# 4_PowerSupplie.net
KiCad netlist of a schematic drawn in Altium Designer
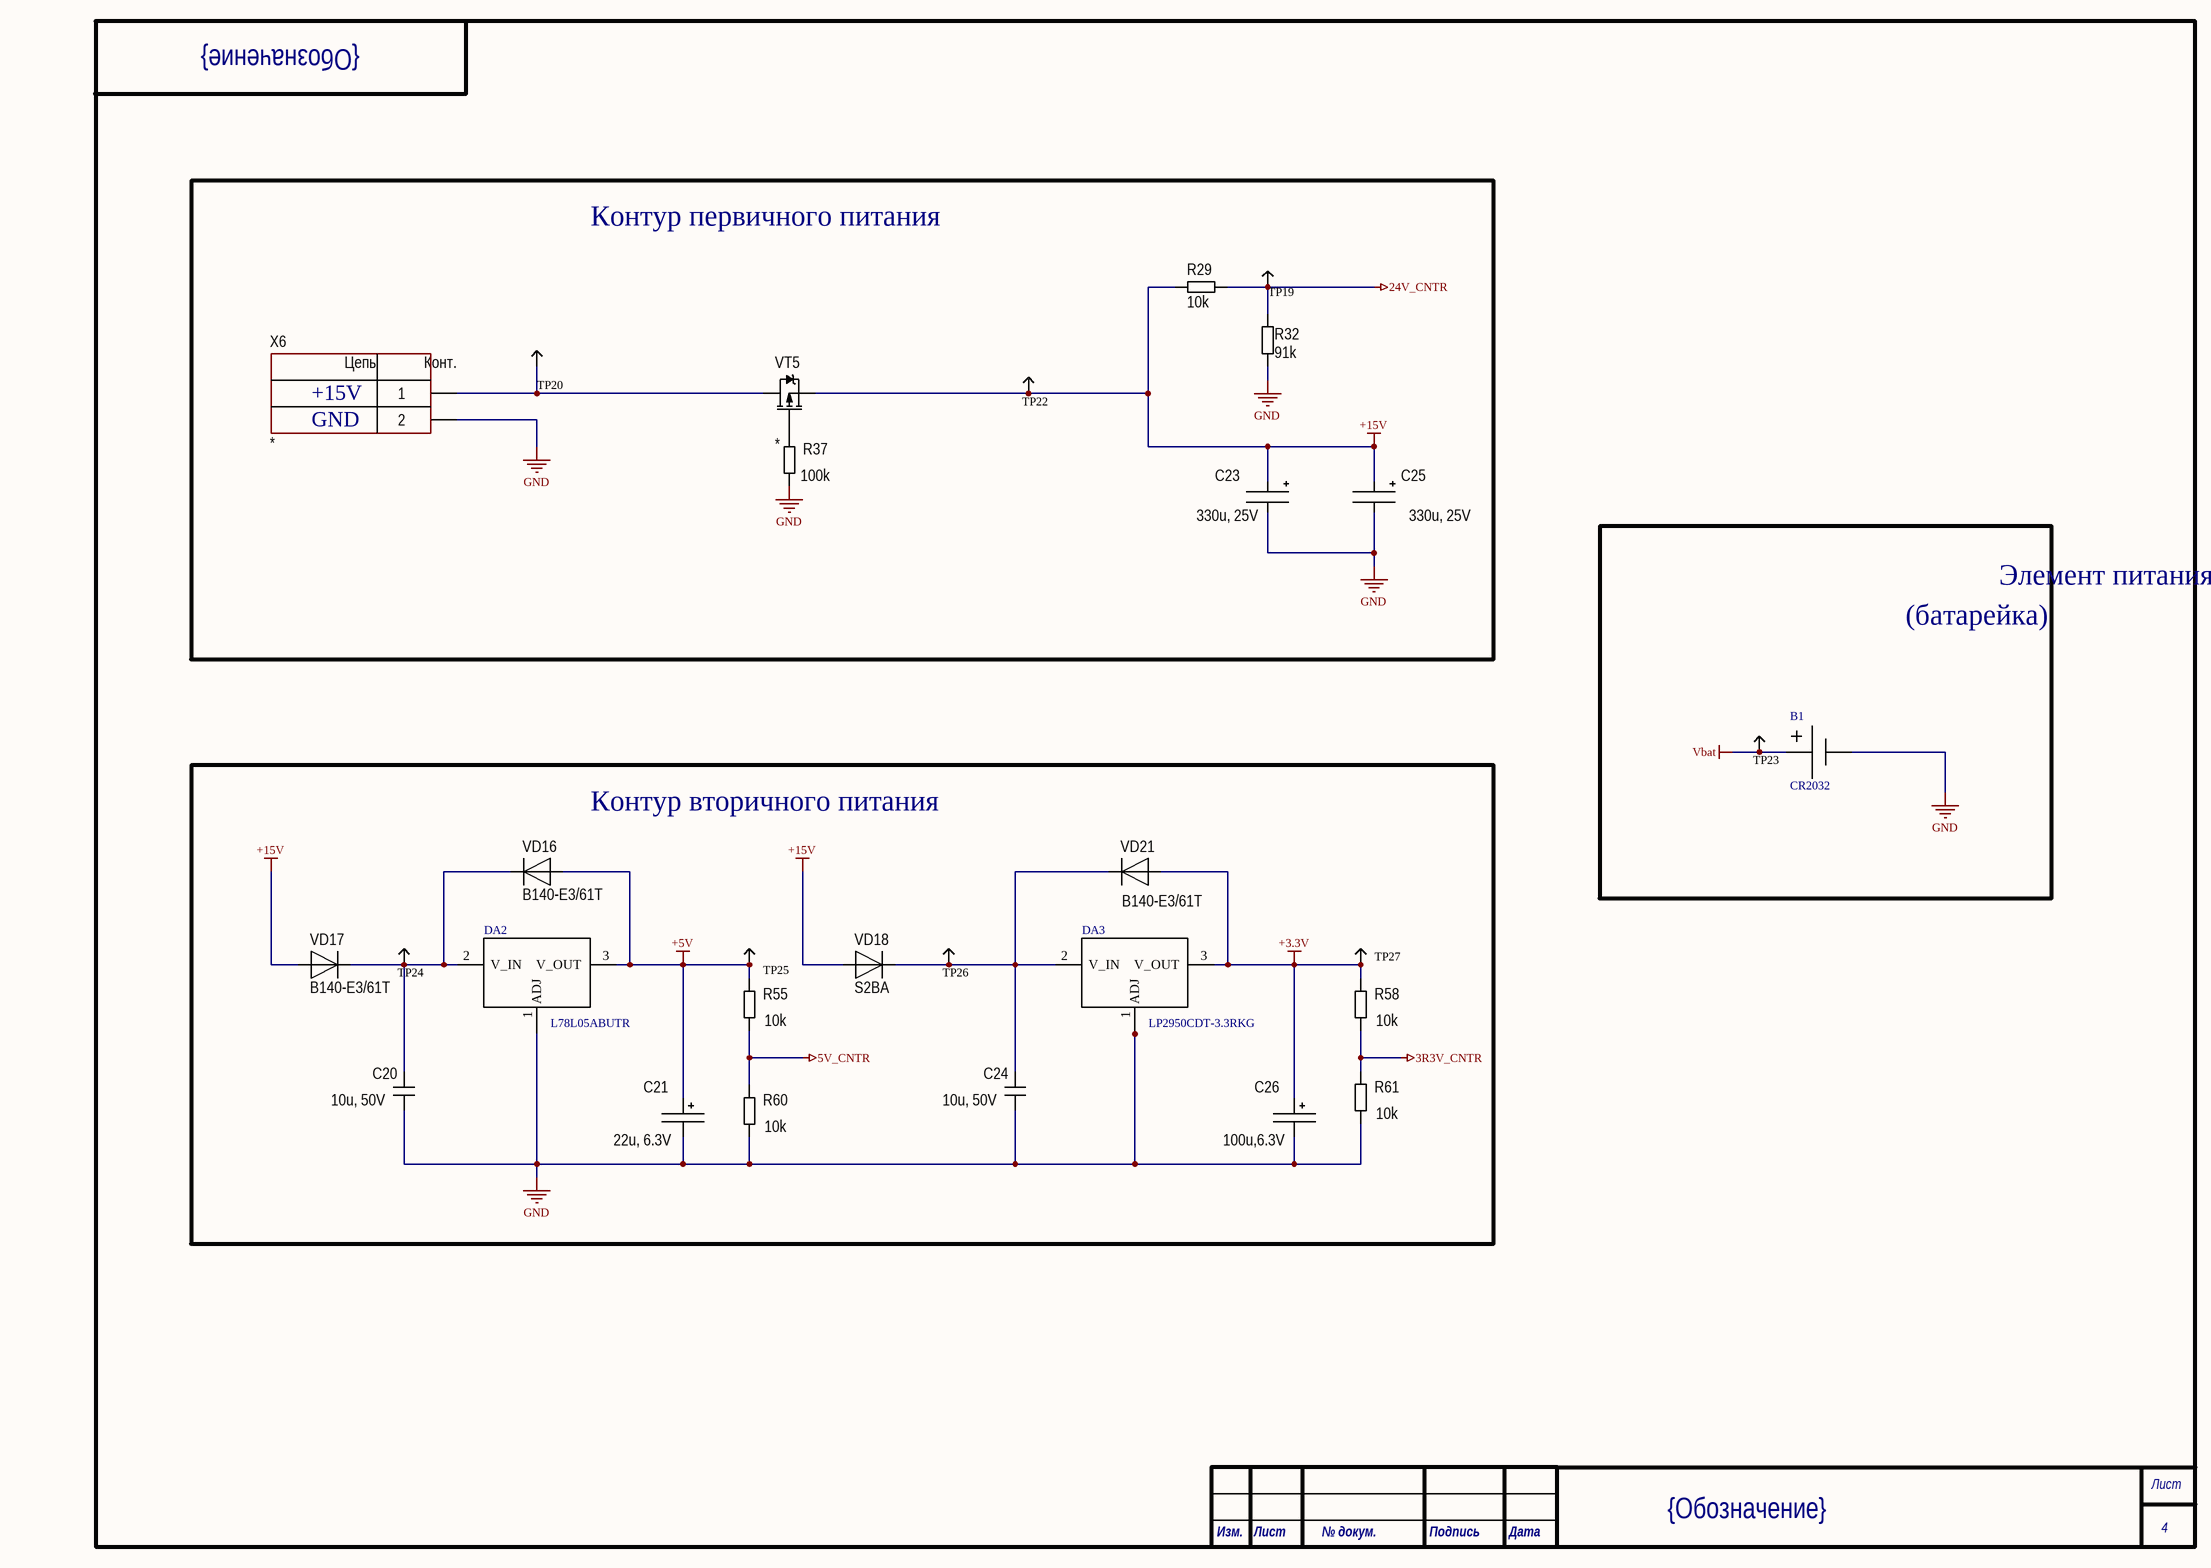
[diagram p0: 4_PowerSupplie.SchDoc]

(export (version "E")
  (design (tool "Eeschema 10.0.6"))
  (components
    (comp (ref "B1")
      (value "CR2032")
      (footprint "BAT: CR2032_SM")
      (libsource (lib "Melochi") (part "Battery_CR2032"))
    )
    (comp (ref "C20")
      (value "10u, 50V")
      (footprint "CH1206C")
      (libsource (lib "Condensators") (part "Capacitor"))
    )
    (comp (ref "C21")
      (value "22u, 6.3V")
      (footprint "TANTAL_A")
      (libsource (lib "Condensators") (part "TantalCap"))
    )
    (comp (ref "C23")
      (value "330u, 25V")
      (footprint "D10C4.4H10")
      (libsource (lib "Condensators") (part "AlumCap"))
    )
    (comp (ref "C24")
      (value "10u, 50V")
      (footprint "CH1206C")
      (libsource (lib "Condensators") (part "Capacitor"))
    )
    (comp (ref "C25")
      (value "330u, 25V")
      (footprint "D10C4.4H10")
      (libsource (lib "Condensators") (part "AlumCap"))
    )
    (comp (ref "C26")
      (value "100u,6.3V")
      (footprint "TANTAL_B")
      (libsource (lib "Condensators") (part "TantalCap"))
    )
    (comp (ref "DA2")
      (value "L78L05ABUTR")
      (footprint "SOT89_PC12120")
      (libsource (lib "MicroIC") (part "LM1117"))
    )
    (comp (ref "DA3")
      (value "LP2950CDT-3.3RKG")
      (footprint "DPAK_213")
      (libsource (lib "MicroIC") (part "LM1117"))
    )
    (comp (ref "R29") (value "10k") (footprint "CH0402R") (libsource (lib "Resistors") (part "Resistor")))
    (comp (ref "R32") (value "91k") (footprint "CH0402R") (libsource (lib "Resistors") (part "Resistor")))
    (comp (ref "R37") (value "100k") (footprint "CH0402R") (libsource (lib "Resistors") (part "Resistor")))
    (comp (ref "R55") (value "10k") (footprint "CH0402R") (libsource (lib "Resistors") (part "Resistor")))
    (comp (ref "R58") (value "10k") (footprint "CH0402R") (libsource (lib "Resistors") (part "Resistor")))
    (comp (ref "R60") (value "10k") (footprint "CH0402R") (libsource (lib "Resistors") (part "Resistor")))
    (comp (ref "R61") (value "10k") (footprint "CH0402R") (libsource (lib "Resistors") (part "Resistor")))
    (comp (ref "TP19") (value "~") (footprint "TestPoint") (libsource (lib "Melochi") (part "TestPoint")))
    (comp (ref "TP20") (value "~") (footprint "TestPoint") (libsource (lib "Melochi") (part "TestPoint")))
    (comp (ref "TP22") (value "~") (footprint "TestPoint") (libsource (lib "Melochi") (part "TestPoint")))
    (comp (ref "TP23") (value "~") (footprint "TestPoint") (libsource (lib "Melochi") (part "TestPoint")))
    (comp (ref "TP24") (value "~") (footprint "TestPoint") (libsource (lib "Melochi") (part "TestPoint")))
    (comp (ref "TP25") (value "~") (footprint "TestPoint") (libsource (lib "Melochi") (part "TestPoint")))
    (comp (ref "TP26") (value "~") (footprint "TestPoint") (libsource (lib "Melochi") (part "TestPoint")))
    (comp (ref "TP27") (value "~") (footprint "TestPoint") (libsource (lib "Melochi") (part "TestPoint")))
    (comp (ref "VD16") (value "B140-E3/61T") (footprint "SMA") (libsource (lib "Diods") (part "Diod")))
    (comp (ref "VD17") (value "B140-E3/61T") (footprint "SMA") (libsource (lib "Diods") (part "Diod")))
    (comp (ref "VD18") (value "S2BA") (footprint "SMA") (libsource (lib "Diods") (part "Diod")))
    (comp (ref "VD21") (value "B140-E3/61T") (footprint "SMA") (libsource (lib "Diods") (part "Diod")))
    (comp (ref "VT5")
      (value "*")
      (footprint "PQFN-3x3")
      (description "Mosfet")
      (libsource (lib "Tranzistor") (part "P-chanel"))
    )
    (comp (ref "X6")
      (value "*")
      (footprint "CON: MX-22-05-3021")
      (libsource (lib "Connectors") (part "2-Connector"))
    )
  )
  (nets
    (net (code "1") (name "+3.3V") (class "Default")
      (node (ref "C26") (pin "1") (pinfunction "1_1") (pintype "power_in"))
      (node (ref "DA3") (pin "3") (pinfunction "V_OUT_3") (pintype "passive"))
      (node (ref "R58") (pin "2") (pinfunction "2_2") (pintype "passive"))
      (node (ref "TP27") (pin "0") (pinfunction "0_0") (pintype "passive"))
      (node (ref "VD21") (pin "1") (pinfunction "1_1") (pintype "passive"))
    )
    (net (code "2") (name "+5V") (class "Default")
      (node (ref "C21") (pin "1") (pinfunction "1_1") (pintype "power_in"))
      (node (ref "DA2") (pin "3") (pinfunction "V_OUT_3") (pintype "passive"))
      (node (ref "R55") (pin "2") (pinfunction "2_2") (pintype "passive"))
      (node (ref "TP25") (pin "0") (pinfunction "0_0") (pintype "passive"))
      (node (ref "VD16") (pin "1") (pinfunction "1_1") (pintype "passive"))
    )
    (net (code "3") (name "+15V") (class "Default")
      (node (ref "C23") (pin "1") (pinfunction "1_1") (pintype "power_in"))
      (node (ref "C25") (pin "1") (pinfunction "1_1") (pintype "power_in"))
      (node (ref "R29") (pin "2") (pinfunction "2_2") (pintype "passive"))
      (node (ref "TP22") (pin "0") (pinfunction "0_0") (pintype "passive"))
      (node (ref "VD17") (pin "1") (pinfunction "1_1") (pintype "passive"))
      (node (ref "VD18") (pin "1") (pinfunction "1_1") (pintype "passive"))
      (node (ref "VT5") (pin "3") (pinfunction "S_3") (pintype "passive"))
    )
    (net (code "4") (name "3R3V_CNTR") (class "Default")
      (node (ref "R58") (pin "1") (pinfunction "1_1") (pintype "passive"))
      (node (ref "R61") (pin "2") (pinfunction "2_2") (pintype "passive"))
    )
    (net (code "5") (name "5V_CNTR") (class "Default")
      (node (ref "R55") (pin "1") (pinfunction "1_1") (pintype "passive"))
      (node (ref "R60") (pin "2") (pinfunction "2_2") (pintype "passive"))
    )
    (net (code "6") (name "24V_CNTR") (class "Default")
      (node (ref "R29") (pin "1") (pinfunction "1_1") (pintype "passive"))
      (node (ref "R32") (pin "2") (pinfunction "2_2") (pintype "passive"))
      (node (ref "TP19") (pin "0") (pinfunction "0_0") (pintype "passive"))
    )
    (net (code "7") (name "GND") (class "Default")
      (node (ref "B1") (pin "2") (pinfunction "2_2") (pintype "passive"))
      (node (ref "C20") (pin "1") (pinfunction "1_1") (pintype "passive"))
      (node (ref "C21") (pin "2") (pinfunction "2_2") (pintype "power_in"))
      (node (ref "C23") (pin "2") (pinfunction "2_2") (pintype "power_in"))
      (node (ref "C24") (pin "1") (pinfunction "1_1") (pintype "passive"))
      (node (ref "C25") (pin "2") (pinfunction "2_2") (pintype "power_in"))
      (node (ref "C26") (pin "2") (pinfunction "2_2") (pintype "power_in"))
      (node (ref "DA2") (pin "1") (pinfunction "ADJ_1") (pintype "passive"))
      (node (ref "DA3") (pin "1") (pinfunction "ADJ_1") (pintype "passive"))
      (node (ref "R32") (pin "1") (pinfunction "1_1") (pintype "passive"))
      (node (ref "R37") (pin "1") (pinfunction "1_1") (pintype "passive"))
      (node (ref "R60") (pin "1") (pinfunction "1_1") (pintype "passive"))
      (node (ref "R61") (pin "1") (pinfunction "1_1") (pintype "passive"))
      (node (ref "X6") (pin "2") (pinfunction "2_2") (pintype "passive"))
    )
    (net (code "8") (name "Net-(DA2-V_IN)") (class "Default")
      (node (ref "C20") (pin "2") (pinfunction "2_2") (pintype "passive"))
      (node (ref "DA2") (pin "2") (pinfunction "V_IN_2") (pintype "passive"))
      (node (ref "TP24") (pin "0") (pinfunction "0_0") (pintype "passive"))
      (node (ref "VD16") (pin "2") (pinfunction "2_2") (pintype "passive"))
      (node (ref "VD17") (pin "2") (pinfunction "2_2") (pintype "passive"))
    )
    (net (code "9") (name "Net-(DA3-V_IN)") (class "Default")
      (node (ref "C24") (pin "2") (pinfunction "2_2") (pintype "passive"))
      (node (ref "DA3") (pin "2") (pinfunction "V_IN_2") (pintype "passive"))
      (node (ref "TP26") (pin "0") (pinfunction "0_0") (pintype "passive"))
      (node (ref "VD18") (pin "2") (pinfunction "2_2") (pintype "passive"))
      (node (ref "VD21") (pin "2") (pinfunction "2_2") (pintype "passive"))
    )
    (net (code "10") (name "Net-(VT5-D)") (class "Default")
      (node (ref "TP20") (pin "0") (pinfunction "0_0") (pintype "passive"))
      (node (ref "VT5") (pin "2") (pinfunction "D_2") (pintype "passive"))
      (node (ref "X6") (pin "1") (pinfunction "1_1") (pintype "passive"))
    )
    (net (code "11") (name "Net-(VT5-G)") (class "Default")
      (node (ref "R37") (pin "2") (pinfunction "2_2") (pintype "passive"))
      (node (ref "VT5") (pin "1") (pinfunction "G_1") (pintype "passive"))
    )
    (net (code "12") (name "Vbat") (class "Default")
      (node (ref "B1") (pin "1") (pinfunction "1_1") (pintype "passive"))
      (node (ref "TP23") (pin "0") (pinfunction "0_0") (pintype "passive"))
    )
  )
)
